# Perif_ricos.net
KiCad netlist of a schematic drawn in Altium Designer
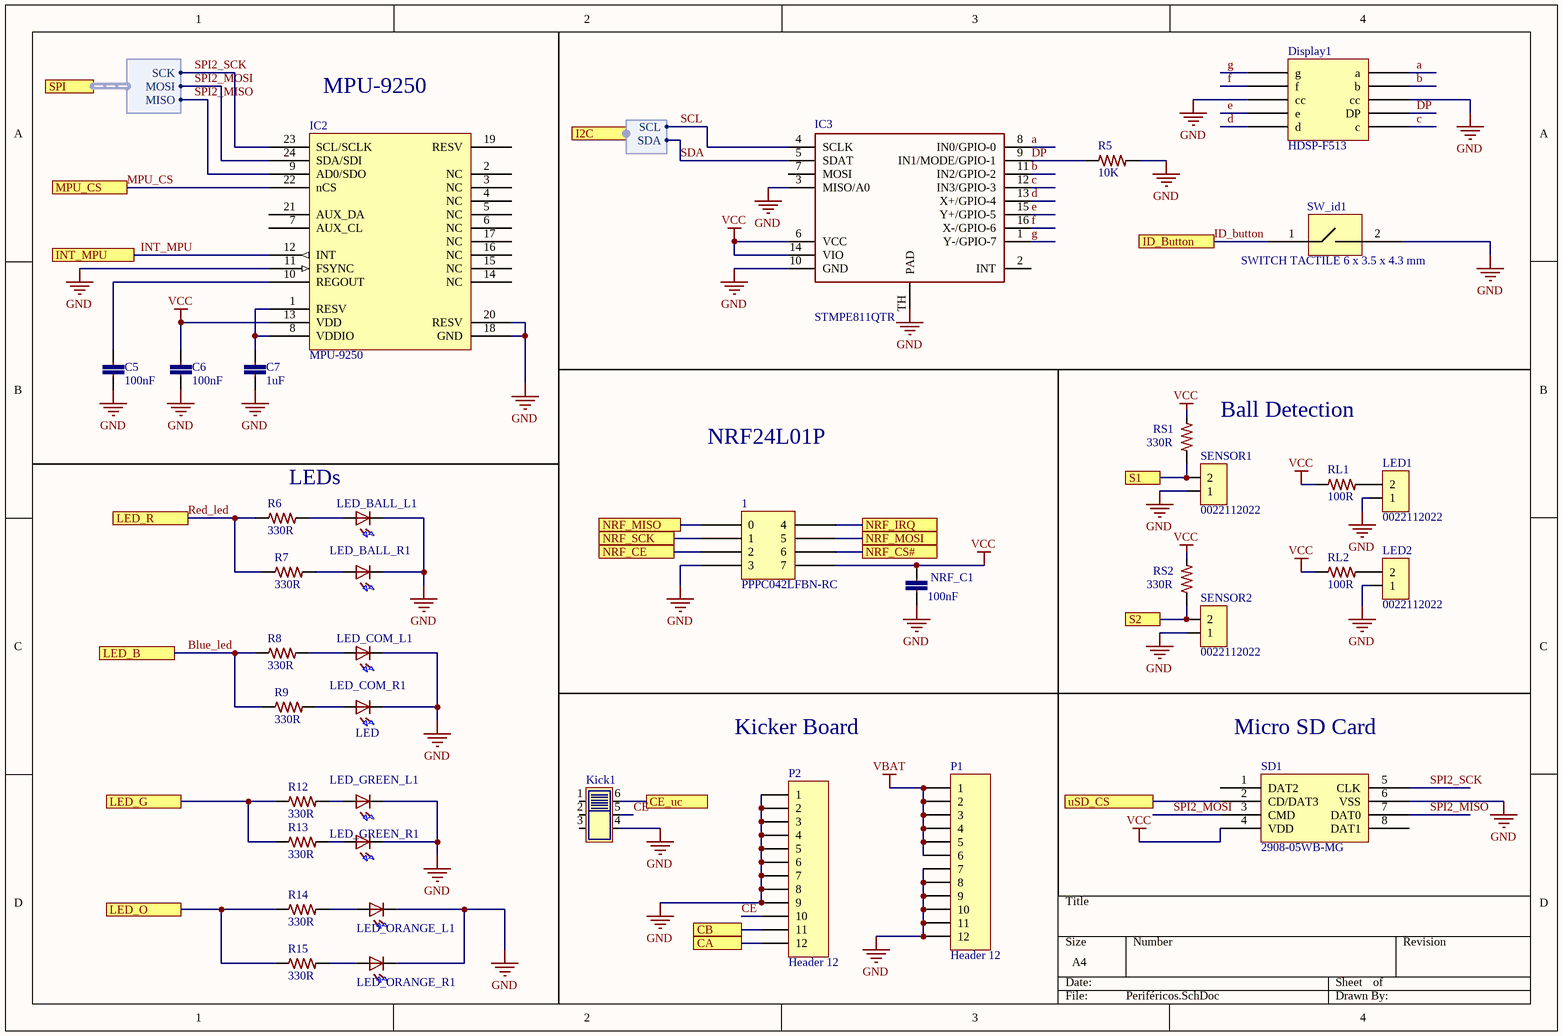
[diagram p0: Periféricos.SchDoc]

(export (version "E")
  (design (tool "Eeschema 10.0.6"))
  (components
    (comp (ref "1")
      (value "PPPC042LFBN-RC")
      (footprint "04x02_Conector_Female")
      (description "8 Position Header Connector 0.100\" (2.54mm) Through Hole Gold")
      (libsource (lib "Schlib1") (part "04x02_Conector_Female"))
    )
    (comp (ref "C5")
      (value "100nF")
      (footprint "0402-CAP")
      (description "CAP CER 0.1UF 10V 20% X5R 0402")
      (fields (field (name "PART NO") "VJ0402V104ZXQPBC"))
      (libsource (lib "IMBEL") (part "CAPACITOR"))
    )
    (comp (ref "C6")
      (value "100nF")
      (footprint "0402-CAP")
      (description "CAP CER 0.1UF 10V 20% X5R 0402")
      (fields (field (name "PART NO") "VJ0402V104ZXQPBC"))
      (libsource (lib "IMBEL") (part "CAPACITOR"))
    )
    (comp (ref "C7")
      (value "1uF")
      (footprint "0402-CAP")
      (description "CAP CER 1UF 6.3V 10% X5R 0402")
      (fields (field (name "PART NO") "JMK105BJ105KV-F"))
      (libsource (lib "IMBEL") (part "CAPACITOR"))
    )
    (comp (ref "Display1")
      (value "HDSP-F513")
      (footprint "New footprint 1")
      (description "7 segments display")
      (libsource (lib "IMBEL") (part "New symbol 1"))
    )
    (comp (ref "IC2")
      (value "MPU-9250")
      (footprint "MPU-9250")
      (description "IMU ACCEL/GYRO/MAG I2C/SPI 24QFN")
      (libsource (lib "") (part "Component_1_2"))
    )
    (comp (ref "IC3")
      (value "STMPE811QTR")
      (footprint "QFN16_N")
      (description "IC TSC I/O EXPAND 8B 16QFN")
      (libsource (lib "IMBEL") (part "STMPE811"))
    )
    (comp (ref "Kick1")
      (value "JS202011SCQN")
      (footprint "SOP250P750X350-6N")
      (description "SWITCH SLIDE DPDT 300MA 6V")
      (libsource (lib "") (part "Component_1_1"))
    )
    (comp (ref "LED1")
      (value "0022112022")
      (footprint "02x01_Conector_Male")
      (description "CONN HEADER 2POS .100 VERT GOLD")
      (libsource (lib "Schlib1") (part "02x01_Conector_Male"))
    )
    (comp (ref "LED2")
      (value "0022112022")
      (footprint "02x01_Conector_Male")
      (description "CONN HEADER 2POS .100 VERT GOLD")
      (libsource (lib "Schlib1") (part "02x01_Conector_Male"))
    )
    (comp (ref "LED_BALL_L1")
      (value "LED")
      (footprint "LED-5MM-PCB")
      (description "LED 5MM PTH")
      (libsource (lib "IMBEL") (part "LED"))
    )
    (comp (ref "LED_BALL_R1")
      (value "LED")
      (footprint "LED-5MM-PCB")
      (description "LED 5MM PTH")
      (libsource (lib "IMBEL") (part "LED"))
    )
    (comp (ref "LED_COM_L1")
      (value "LED")
      (footprint "LED-5MM-PCB")
      (description "LED 5MM PTH")
      (libsource (lib "IMBEL") (part "LED"))
    )
    (comp (ref "LED_COM_R1")
      (value "LED")
      (footprint "LED-5MM-PCB")
      (description "LED 5MM PTH")
      (libsource (lib "IMBEL") (part "LED"))
    )
    (comp (ref "LED_GREEN_L1")
      (value "LED")
      (footprint "LED-5MM-PCB")
      (description "LED 5MM PTH")
      (libsource (lib "IMBEL") (part "LED"))
    )
    (comp (ref "LED_GREEN_R1")
      (value "LED")
      (footprint "LED-5MM-PCB")
      (description "LED 5MM PTH")
      (libsource (lib "IMBEL") (part "LED"))
    )
    (comp (ref "LED_ORANGE_L1")
      (value "LED")
      (footprint "LED-5MM-PCB")
      (description "LED 5MM PTH")
      (libsource (lib "IMBEL") (part "LED"))
    )
    (comp (ref "LED_ORANGE_R1")
      (value "LED")
      (footprint "LED-5MM-PCB")
      (description "LED 5MM PTH")
      (libsource (lib "IMBEL") (part "LED"))
    )
    (comp (ref "NRF_C1")
      (value "100nF")
      (footprint "0402-CAP")
      (description "CAP CER 0.1UF 10V 20% X5R 0402")
      (fields (field (name "PART NO") "VJ0402V104ZXQPBC"))
      (libsource (lib "IMBEL") (part "CC0402-100nF-A.12"))
    )
    (comp (ref "P1")
      (value "Header 12")
      (footprint "HDR1X12")
      (description "Header, 12-Pin")
      (fields (field (name "PUBLISHER") "Altium Limited"))
      (libsource (lib "Miscellaneous Connectors") (part "Header 12"))
    )
    (comp (ref "P2")
      (value "Header 12")
      (footprint "HDR1X12")
      (description "Header, 12-Pin")
      (fields (field (name "PUBLISHER") "Altium Limited"))
      (libsource (lib "Miscellaneous Connectors") (part "Header 12"))
    )
    (comp (ref "R5")
      (value "10K")
      (footprint "0402-RES-HD")
      (description "RES 10K OHM 1/10W 1% 0402 SMD")
      (fields (field (name "PART NO") "ERJ-2RKF1002X"))
      (libsource (lib "IMBEL") (part "RESISTOR"))
    )
    (comp (ref "R6")
      (value "330R")
      (footprint "0402-RES-HD")
      (description "RES 330 OHM 1/10W 1% 0402 SMD")
      (fields (field (name "PART NO") "ERJ-2RKF3300X"))
      (libsource (lib "IMBEL") (part "RESISTOR"))
    )
    (comp (ref "R7")
      (value "330R")
      (footprint "0402-RES-HD")
      (description "RES 330 OHM 1/10W 1% 0402 SMD")
      (fields (field (name "PART NO") "ERJ-2RKF3300X"))
      (libsource (lib "IMBEL") (part "RESISTOR"))
    )
    (comp (ref "R8")
      (value "330R")
      (footprint "0402-RES-HD")
      (description "RES 330 OHM 1/10W 1% 0402 SMD")
      (fields (field (name "PART NO") "ERJ-2RKF3300X"))
      (libsource (lib "IMBEL") (part "RESISTOR"))
    )
    (comp (ref "R9")
      (value "330R")
      (footprint "0402-RES-HD")
      (description "RES 330 OHM 1/10W 1% 0402 SMD")
      (fields (field (name "PART NO") "ERJ-2RKF3300X"))
      (libsource (lib "IMBEL") (part "RESISTOR"))
    )
    (comp (ref "R12")
      (value "330R")
      (footprint "0402-RES-HD")
      (description "RES 330 OHM 1/10W 1% 0402 SMD")
      (fields (field (name "PART NO") "ERJ-2RKF3300X"))
      (libsource (lib "IMBEL") (part "RESISTOR"))
    )
    (comp (ref "R13")
      (value "330R")
      (footprint "0402-RES-HD")
      (description "RES 330 OHM 1/10W 1% 0402 SMD")
      (fields (field (name "PART NO") "ERJ-2RKF3300X"))
      (libsource (lib "IMBEL") (part "RESISTOR"))
    )
    (comp (ref "R14")
      (value "330R")
      (footprint "0402-RES-HD")
      (description "RES 330 OHM 1/10W 1% 0402 SMD")
      (fields (field (name "PART NO") "ERJ-2RKF3300X"))
      (libsource (lib "IMBEL") (part "RESISTOR"))
    )
    (comp (ref "R15")
      (value "330R")
      (footprint "0402-RES-HD")
      (description "RES 330 OHM 1/10W 1% 0402 SMD")
      (fields (field (name "PART NO") "ERJ-2RKF3300X"))
      (libsource (lib "IMBEL") (part "RESISTOR"))
    )
    (comp (ref "RL1")
      (value "100R")
      (footprint "0402-RES-HD")
      (description "RES 100 OHM 1/10W 1% 0402 SMD")
      (fields (field (name "PART NO") "ERJ-2RKF1000X"))
      (libsource (lib "IMBEL") (part "RESISTOR"))
    )
    (comp (ref "RL2")
      (value "100R")
      (footprint "0402-RES-HD")
      (description "RES 100 OHM 1/10W 1% 0402 SMD")
      (fields (field (name "PART NO") "ERJ-2RKF1000X"))
      (libsource (lib "IMBEL") (part "RESISTOR"))
    )
    (comp (ref "RS1")
      (value "330R")
      (footprint "0402-RES-HD")
      (description "RES 330 OHM 1/10W 1% 0402 SMD")
      (fields (field (name "PART NO") "ERJ-2RKF3300X"))
      (libsource (lib "IMBEL") (part "RESISTOR"))
    )
    (comp (ref "RS2")
      (value "330R")
      (footprint "0402-RES-HD")
      (description "RES 330 OHM 1/10W 1% 0402 SMD")
      (fields (field (name "PART NO") "ERJ-2RKF3300X"))
      (libsource (lib "IMBEL") (part "RESISTOR"))
    )
    (comp (ref "SD1")
      (value "2908-05WB-MG")
      (footprint "New footprint 1")
      (description "CONN MICRO SD CARD PUSH-PUSH R/A")
      (libsource (lib "IMBEL") (part "SD-CON-SCH"))
    )
    (comp (ref "SENSOR1")
      (value "0022112022")
      (footprint "02x01_Conector_Male")
      (description "CONN HEADER 2POS .100 VERT GOLD")
      (libsource (lib "Schlib1") (part "02x01_Conector_Male"))
    )
    (comp (ref "SENSOR2")
      (value "0022112022")
      (footprint "02x01_Conector_Male")
      (description "CONN HEADER 2POS .100 VERT GOLD")
      (libsource (lib "Schlib1") (part "02x01_Conector_Male"))
    )
    (comp (ref "SW_id1")
      (value "SWITCH TACTILE 6 x 3.5 x 4.3 mm")
      (footprint "PCBComponent")
      (description "GRAYHILL TACT,GW,6X3.5,1800T&R,LF Eight, 160g Operating Force, Gull Wing, RoHS Compliant")
      (fields (field (name "PART NO") "95C04A3GWRT"))
      (libsource (lib "IMBEL") (part "Component_1"))
    )
  )
  (nets
    (net (code "3") (name "/Blue_led") (class "Default")
      (node (ref "R8") (pin "1") (pinfunction "1_1") (pintype "passive"))
      (node (ref "R9") (pin "1") (pinfunction "1_1") (pintype "passive"))
    )
    (net (code "4") (name "/CA") (class "Default")
      (node (ref "P2") (pin "12") (pinfunction "12_12") (pintype "passive"))
    )
    (net (code "5") (name "/CB") (class "Default")
      (node (ref "P2") (pin "11") (pinfunction "11_11") (pintype "passive"))
    )
    (net (code "6") (name "/CE") (class "Default")
      (node (ref "Kick1") (pin "5") (pintype "passive"))
      (node (ref "P2") (pin "10") (pinfunction "10_10") (pintype "passive"))
    )
    (net (code "7") (name "/CE_uc") (class "Default") (node (ref "Kick1") (pin "6") (pintype "passive")))
    (net (code "8") (name "/DP") (class "Default")
      (node (ref "Display1") (pin "9") (pinfunction "DP_9") (pintype "passive"))
      (node (ref "IC3") (pin "9") (pinfunction "IN1/MODE/GPIO-1_9") (pintype "passive"))
      (node (ref "R5") (pin "1") (pinfunction "1_1") (pintype "passive"))
    )
    (net (code "9") (name "/ID_button") (class "Default")
      (node (ref "SW_id1") (pin "1") (pinfunction "1_1") (pintype "passive"))
    )
    (net (code "10") (name "/INT_MPU") (class "Default")
      (node (ref "IC2") (pin "12") (pinfunction "INT_12") (pintype "output"))
    )
    (net (code "11") (name "/LED_G") (class "Default")
      (node (ref "R12") (pin "1") (pinfunction "1_1") (pintype "passive"))
      (node (ref "R13") (pin "1") (pinfunction "1_1") (pintype "passive"))
    )
    (net (code "12") (name "/LED_O") (class "Default")
      (node (ref "R14") (pin "1") (pinfunction "1_1") (pintype "passive"))
      (node (ref "R15") (pin "1") (pinfunction "1_1") (pintype "passive"))
    )
    (net (code "13") (name "/MPU_CS") (class "Default")
      (node (ref "IC2") (pin "22") (pinfunction "nCS_22") (pintype "passive"))
    )
    (net (code "14") (name "/NRF_CE") (class "Default")
      (node (ref "1") (pin "2") (pinfunction "2_2") (pintype "passive"))
    )
    (net (code "15") (name "/NRF_CS#") (class "Default")
      (node (ref "1") (pin "6") (pinfunction "6_6") (pintype "passive"))
    )
    (net (code "16") (name "/NRF_IRQ") (class "Default")
      (node (ref "1") (pin "4") (pinfunction "4_4") (pintype "passive"))
    )
    (net (code "17") (name "/NRF_MISO") (class "Default")
      (node (ref "1") (pin "0") (pinfunction "0_0") (pintype "passive"))
    )
    (net (code "18") (name "/NRF_MOSI") (class "Default")
      (node (ref "1") (pin "5") (pinfunction "5_5") (pintype "passive"))
    )
    (net (code "19") (name "/NRF_SCK") (class "Default")
      (node (ref "1") (pin "1") (pinfunction "1_1") (pintype "passive"))
    )
    (net (code "20") (name "/Red_led") (class "Default")
      (node (ref "R6") (pin "1") (pinfunction "1_1") (pintype "passive"))
      (node (ref "R7") (pin "1") (pinfunction "1_1") (pintype "passive"))
    )
    (net (code "21") (name "/S1") (class "Default")
      (node (ref "RS1") (pin "1") (pinfunction "1_1") (pintype "passive"))
      (node (ref "SENSOR1") (pin "2") (pinfunction "2_2") (pintype "passive"))
    )
    (net (code "22") (name "/S2") (class "Default")
      (node (ref "RS2") (pin "1") (pinfunction "1_1") (pintype "passive"))
      (node (ref "SENSOR2") (pin "2") (pinfunction "2_2") (pintype "passive"))
    )
    (net (code "23") (name "/SCL") (class "Default")
      (node (ref "IC3") (pin "4") (pinfunction "SCLK_4") (pintype "passive"))
    )
    (net (code "24") (name "/SDA") (class "Default")
      (node (ref "IC3") (pin "5") (pinfunction "SDAT_5") (pintype "passive"))
    )
    (net (code "25") (name "/SPI2_MISO") (class "Default")
      (node (ref "IC2") (pin "9") (pinfunction "AD0/SDO_9") (pintype "passive"))
      (node (ref "SD1") (pin "7") (pinfunction "DAT0_7") (pintype "passive"))
    )
    (net (code "26") (name "/SPI2_MOSI") (class "Default")
      (node (ref "IC2") (pin "24") (pinfunction "SDA/SDI_24") (pintype "passive"))
      (node (ref "SD1") (pin "3") (pinfunction "CMD_3") (pintype "passive"))
    )
    (net (code "27") (name "/SPI2_SCK") (class "Default")
      (node (ref "IC2") (pin "23") (pinfunction "SCL/SCLK_23") (pintype "passive"))
      (node (ref "SD1") (pin "5") (pinfunction "CLK_5") (pintype "passive"))
    )
    (net (code "28") (name "/a") (class "Default")
      (node (ref "Display1") (pin "6") (pinfunction "a_6") (pintype "passive"))
      (node (ref "IC3") (pin "8") (pinfunction "IN0/GPIO-0_8") (pintype "passive"))
    )
    (net (code "29") (name "/b") (class "Default")
      (node (ref "Display1") (pin "7") (pinfunction "b_7") (pintype "passive"))
      (node (ref "IC3") (pin "11") (pinfunction "IN2/GPIO-2_11") (pintype "passive"))
    )
    (net (code "30") (name "/c") (class "Default")
      (node (ref "Display1") (pin "10") (pinfunction "c_10") (pintype "passive"))
      (node (ref "IC3") (pin "12") (pinfunction "IN3/GPIO-3_12") (pintype "passive"))
    )
    (net (code "31") (name "/d") (class "Default")
      (node (ref "Display1") (pin "5") (pinfunction "d_5") (pintype "passive"))
      (node (ref "IC3") (pin "13") (pinfunction "X+/GPIO-4_13") (pintype "passive"))
    )
    (net (code "32") (name "/e") (class "Default")
      (node (ref "Display1") (pin "4") (pinfunction "e_4") (pintype "passive"))
      (node (ref "IC3") (pin "15") (pinfunction "Y+/GPIO-5_15") (pintype "passive"))
    )
    (net (code "33") (name "/f") (class "Default")
      (node (ref "Display1") (pin "2") (pinfunction "f_2") (pintype "passive"))
      (node (ref "IC3") (pin "16") (pinfunction "X-/GPIO-6_16") (pintype "passive"))
    )
    (net (code "34") (name "/g") (class "Default")
      (node (ref "Display1") (pin "1") (pinfunction "g_1") (pintype "passive"))
      (node (ref "IC3") (pin "1") (pinfunction "Y-/GPIO-7_1") (pintype "passive"))
    )
    (net (code "35") (name "/uSD_CS") (class "Default")
      (node (ref "SD1") (pin "2") (pinfunction "CD/DAT3_2") (pintype "passive"))
    )
    (net (code "38") (name "GND") (class "Default")
      (node (ref "1") (pin "3") (pinfunction "3_3") (pintype "passive"))
      (node (ref "C5") (pin "2") (pinfunction "2_2") (pintype "passive"))
      (node (ref "C6") (pin "2") (pinfunction "2_2") (pintype "passive"))
      (node (ref "C7") (pin "2") (pinfunction "2_2") (pintype "passive"))
      (node (ref "Display1") (pin "3") (pinfunction "cc_3") (pintype "passive"))
      (node (ref "Display1") (pin "8") (pinfunction "cc_8") (pintype "passive"))
      (node (ref "IC2") (pin "11") (pinfunction "FSYNC_11") (pintype "input"))
      (node (ref "IC2") (pin "18") (pinfunction "GND_18") (pintype "power_in"))
      (node (ref "IC2") (pin "20") (pinfunction "RESV_20") (pintype "passive"))
      (node (ref "IC3") (pin "10") (pinfunction "GND_10") (pintype "passive"))
      (node (ref "IC3") (pin "3") (pinfunction "MISO/A0_3") (pintype "passive"))
      (node (ref "IC3") (pin "TH") (pinfunction "PAD_TH") (pintype "passive"))
      (node (ref "Kick1") (pin "4") (pintype "passive"))
      (node (ref "LED1") (pin "1") (pinfunction "1_1") (pintype "passive"))
      (node (ref "LED2") (pin "1") (pinfunction "1_1") (pintype "passive"))
      (node (ref "LED_BALL_L1") (pin "1") (pinfunction "K_1") (pintype "passive"))
      (node (ref "LED_BALL_R1") (pin "1") (pinfunction "K_1") (pintype "passive"))
      (node (ref "LED_COM_L1") (pin "1") (pinfunction "K_1") (pintype "passive"))
      (node (ref "LED_COM_R1") (pin "1") (pinfunction "K_1") (pintype "passive"))
      (node (ref "LED_GREEN_L1") (pin "1") (pinfunction "K_1") (pintype "passive"))
      (node (ref "LED_GREEN_R1") (pin "1") (pinfunction "K_1") (pintype "passive"))
      (node (ref "LED_ORANGE_L1") (pin "1") (pinfunction "K_1") (pintype "passive"))
      (node (ref "LED_ORANGE_R1") (pin "1") (pinfunction "K_1") (pintype "passive"))
      (node (ref "NRF_C1") (pin "2") (pinfunction "2_2") (pintype "passive"))
      (node (ref "P1") (pin "10") (pinfunction "10_10") (pintype "passive"))
      (node (ref "P1") (pin "11") (pinfunction "11_11") (pintype "passive"))
      (node (ref "P1") (pin "12") (pinfunction "12_12") (pintype "passive"))
      (node (ref "P1") (pin "7") (pinfunction "7_7") (pintype "passive"))
      (node (ref "P1") (pin "8") (pinfunction "8_8") (pintype "passive"))
      (node (ref "P1") (pin "9") (pinfunction "9_9") (pintype "passive"))
      (node (ref "P2") (pin "1") (pinfunction "1_1") (pintype "passive"))
      (node (ref "P2") (pin "2") (pinfunction "2_2") (pintype "passive"))
      (node (ref "P2") (pin "3") (pinfunction "3_3") (pintype "passive"))
      (node (ref "P2") (pin "4") (pinfunction "4_4") (pintype "passive"))
      (node (ref "P2") (pin "5") (pinfunction "5_5") (pintype "passive"))
      (node (ref "P2") (pin "6") (pinfunction "6_6") (pintype "passive"))
      (node (ref "P2") (pin "7") (pinfunction "7_7") (pintype "passive"))
      (node (ref "P2") (pin "8") (pinfunction "8_8") (pintype "passive"))
      (node (ref "P2") (pin "9") (pinfunction "9_9") (pintype "passive"))
      (node (ref "R5") (pin "2") (pinfunction "2_2") (pintype "passive"))
      (node (ref "SD1") (pin "6") (pinfunction "VSS_6") (pintype "passive"))
      (node (ref "SENSOR1") (pin "1") (pinfunction "1_1") (pintype "passive"))
      (node (ref "SENSOR2") (pin "1") (pinfunction "1_1") (pintype "passive"))
      (node (ref "SW_id1") (pin "2") (pinfunction "2_2") (pintype "passive"))
    )
    (net (code "39") (name "Net-(IC2-REGOUT)") (class "Default")
      (node (ref "C5") (pin "1") (pinfunction "1_1") (pintype "passive"))
      (node (ref "IC2") (pin "10") (pinfunction "REGOUT_10") (pintype "passive"))
    )
    (net (code "40") (name "Net-(IC2-VDDIO)") (class "Default")
      (node (ref "C7") (pin "1") (pinfunction "1_1") (pintype "passive"))
      (node (ref "IC2") (pin "1") (pinfunction "RESV_1") (pintype "passive"))
      (node (ref "IC2") (pin "8") (pinfunction "VDDIO_8") (pintype "power_in"))
    )
    (net (code "41") (name "Net-(LED1-Pad2)") (class "Default")
      (node (ref "LED1") (pin "2") (pinfunction "2_2") (pintype "passive"))
      (node (ref "RL1") (pin "2") (pinfunction "2_2") (pintype "passive"))
    )
    (net (code "42") (name "Net-(LED2-Pad2)") (class "Default")
      (node (ref "LED2") (pin "2") (pinfunction "2_2") (pintype "passive"))
      (node (ref "RL2") (pin "2") (pinfunction "2_2") (pintype "passive"))
    )
    (net (code "43") (name "Net-(LED_BALL_L1-A)") (class "Default")
      (node (ref "LED_BALL_L1") (pin "2") (pinfunction "A_2") (pintype "passive"))
      (node (ref "R6") (pin "2") (pinfunction "2_2") (pintype "passive"))
    )
    (net (code "44") (name "Net-(LED_BALL_R1-A)") (class "Default")
      (node (ref "LED_BALL_R1") (pin "2") (pinfunction "A_2") (pintype "passive"))
      (node (ref "R7") (pin "2") (pinfunction "2_2") (pintype "passive"))
    )
    (net (code "45") (name "Net-(LED_COM_L1-A)") (class "Default")
      (node (ref "LED_COM_L1") (pin "2") (pinfunction "A_2") (pintype "passive"))
      (node (ref "R8") (pin "2") (pinfunction "2_2") (pintype "passive"))
    )
    (net (code "46") (name "Net-(LED_COM_R1-A)") (class "Default")
      (node (ref "LED_COM_R1") (pin "2") (pinfunction "A_2") (pintype "passive"))
      (node (ref "R9") (pin "2") (pinfunction "2_2") (pintype "passive"))
    )
    (net (code "47") (name "Net-(LED_GREEN_L1-A)") (class "Default")
      (node (ref "LED_GREEN_L1") (pin "2") (pinfunction "A_2") (pintype "passive"))
      (node (ref "R12") (pin "2") (pinfunction "2_2") (pintype "passive"))
    )
    (net (code "48") (name "Net-(LED_GREEN_R1-A)") (class "Default")
      (node (ref "LED_GREEN_R1") (pin "2") (pinfunction "A_2") (pintype "passive"))
      (node (ref "R13") (pin "2") (pinfunction "2_2") (pintype "passive"))
    )
    (net (code "49") (name "Net-(LED_ORANGE_L1-A)") (class "Default")
      (node (ref "LED_ORANGE_L1") (pin "2") (pinfunction "A_2") (pintype "passive"))
      (node (ref "R14") (pin "2") (pinfunction "2_2") (pintype "passive"))
    )
    (net (code "50") (name "Net-(LED_ORANGE_R1-A)") (class "Default")
      (node (ref "LED_ORANGE_R1") (pin "2") (pinfunction "A_2") (pintype "passive"))
      (node (ref "R15") (pin "2") (pinfunction "2_2") (pintype "passive"))
    )
    (net (code "51") (name "VBAT") (class "Default")
      (node (ref "P1") (pin "1") (pinfunction "1_1") (pintype "passive"))
      (node (ref "P1") (pin "2") (pinfunction "2_2") (pintype "passive"))
      (node (ref "P1") (pin "3") (pinfunction "3_3") (pintype "passive"))
      (node (ref "P1") (pin "4") (pinfunction "4_4") (pintype "passive"))
      (node (ref "P1") (pin "5") (pinfunction "5_5") (pintype "passive"))
      (node (ref "P1") (pin "6") (pinfunction "6_6") (pintype "passive"))
    )
    (net (code "52") (name "VCC") (class "Default")
      (node (ref "1") (pin "7") (pinfunction "7_7") (pintype "passive"))
      (node (ref "C6") (pin "1") (pinfunction "1_1") (pintype "passive"))
      (node (ref "IC2") (pin "13") (pinfunction "VDD_13") (pintype "power_in"))
      (node (ref "IC3") (pin "14") (pinfunction "VIO_14") (pintype "passive"))
      (node (ref "IC3") (pin "6") (pinfunction "VCC_6") (pintype "passive"))
      (node (ref "NRF_C1") (pin "1") (pinfunction "1_1") (pintype "passive"))
      (node (ref "RL1") (pin "1") (pinfunction "1_1") (pintype "passive"))
      (node (ref "RL2") (pin "1") (pinfunction "1_1") (pintype "passive"))
      (node (ref "RS1") (pin "2") (pinfunction "2_2") (pintype "passive"))
      (node (ref "RS2") (pin "2") (pinfunction "2_2") (pintype "passive"))
      (node (ref "SD1") (pin "4") (pinfunction "VDD_4") (pintype "passive"))
    )
    (net (code "53") (name "unconnected-(IC2-AUX_CL-Pad7)") (class "Default")
      (node (ref "IC2") (pin "7") (pinfunction "AUX_CL_7") (pintype "passive"))
    )
    (net (code "54") (name "unconnected-(IC2-AUX_DA-Pad21)") (class "Default")
      (node (ref "IC2") (pin "21") (pinfunction "AUX_DA_21") (pintype "passive"))
    )
    (net (code "55") (name "unconnected-(IC2-NC-Pad2)") (class "Default")
      (node (ref "IC2") (pin "2") (pinfunction "NC_2") (pintype "passive"))
    )
    (net (code "56") (name "unconnected-(IC2-NC-Pad3)") (class "Default")
      (node (ref "IC2") (pin "3") (pinfunction "NC_3") (pintype "passive"))
    )
    (net (code "57") (name "unconnected-(IC2-NC-Pad4)") (class "Default")
      (node (ref "IC2") (pin "4") (pinfunction "NC_4") (pintype "passive"))
    )
    (net (code "58") (name "unconnected-(IC2-NC-Pad5)") (class "Default")
      (node (ref "IC2") (pin "5") (pinfunction "NC_5") (pintype "passive"))
    )
    (net (code "59") (name "unconnected-(IC2-NC-Pad6)") (class "Default")
      (node (ref "IC2") (pin "6") (pinfunction "NC_6") (pintype "passive"))
    )
    (net (code "60") (name "unconnected-(IC2-NC-Pad14)") (class "Default")
      (node (ref "IC2") (pin "14") (pinfunction "NC_14") (pintype "passive"))
    )
    (net (code "61") (name "unconnected-(IC2-NC-Pad15)") (class "Default")
      (node (ref "IC2") (pin "15") (pinfunction "NC_15") (pintype "passive"))
    )
    (net (code "62") (name "unconnected-(IC2-NC-Pad16)") (class "Default")
      (node (ref "IC2") (pin "16") (pinfunction "NC_16") (pintype "passive"))
    )
    (net (code "63") (name "unconnected-(IC2-NC-Pad17)") (class "Default")
      (node (ref "IC2") (pin "17") (pinfunction "NC_17") (pintype "passive"))
    )
    (net (code "64") (name "unconnected-(IC2-RESV-Pad19)") (class "Default")
      (node (ref "IC2") (pin "19") (pinfunction "RESV_19") (pintype "passive"))
    )
    (net (code "65") (name "unconnected-(IC3-INT-Pad2)") (class "Default")
      (node (ref "IC3") (pin "2") (pinfunction "INT_2") (pintype "passive"))
    )
    (net (code "66") (name "unconnected-(IC3-MOSI-Pad7)") (class "Default")
      (node (ref "IC3") (pin "7") (pinfunction "MOSI_7") (pintype "passive"))
    )
    (net (code "67") (name "unconnected-(Kick1-Pad1)") (class "Default")
      (node (ref "Kick1") (pin "1") (pintype "passive"))
    )
    (net (code "68") (name "unconnected-(Kick1-Pad2)") (class "Default")
      (node (ref "Kick1") (pin "2") (pintype "passive"))
    )
    (net (code "69") (name "unconnected-(Kick1-Pad3)") (class "Default")
      (node (ref "Kick1") (pin "3") (pintype "passive"))
    )
    (net (code "70") (name "unconnected-(SD1-DAT1-Pad8)") (class "Default")
      (node (ref "SD1") (pin "8") (pinfunction "DAT1_8") (pintype "passive"))
    )
    (net (code "71") (name "unconnected-(SD1-DAT2-Pad1)") (class "Default")
      (node (ref "SD1") (pin "1") (pinfunction "DAT2_1") (pintype "passive"))
    )
  )
)
